# Audio-Beamformer_Supply_V1_0.net
KiCad netlist of a schematic drawn in Altium Designer
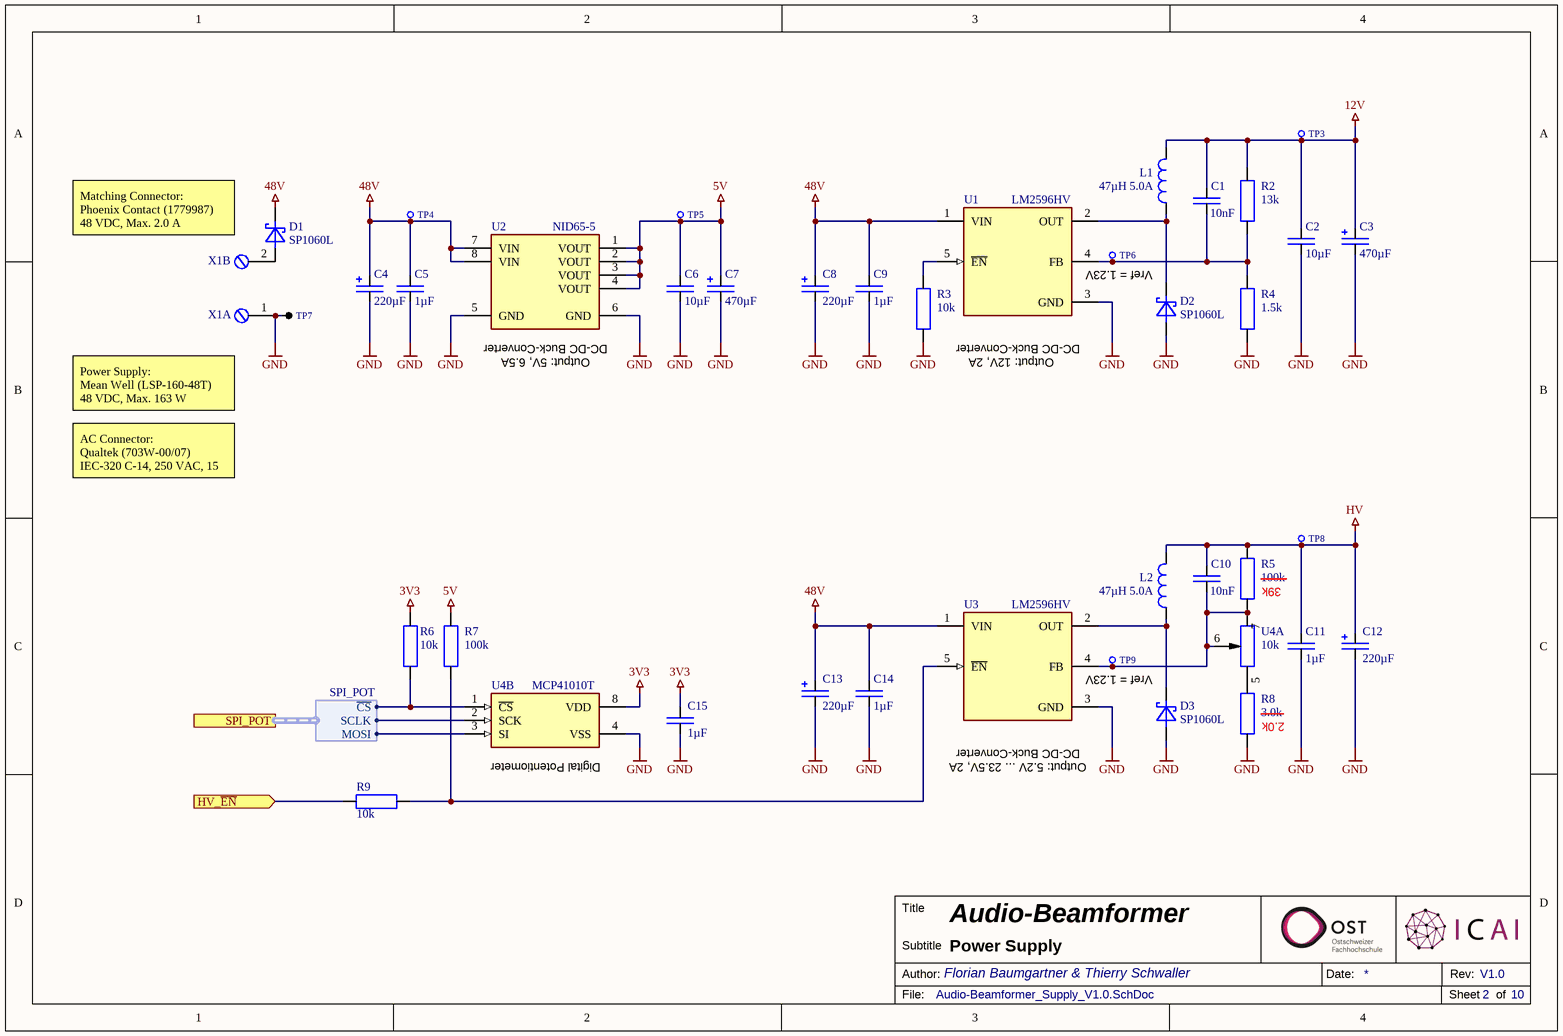
[diagram p0: Audio-Beamformer_Supply_V1.0.SchDoc]

(export (version "E")
  (design (tool "Eeschema 10.0.6"))
  (components
    (comp (ref "C1")
      (value "10nF")
      (footprint "SMD Keramikkondensator 0603")
      (description "SMD Ceramic Capacitor E6")
      (libsource (lib "Ceramic Capacitors-E6") (part "E6 - 10nF"))
    )
    (comp (ref "C2")
      (value "10µF")
      (footprint "SMD Keramikkondensator 1206")
      (description "CAP-MK")
      (libsource (lib "AudioAmp") (part "C-CAPACITOR"))
    )
    (comp (ref "C3")
      (value "470µF")
      (footprint "SMD Elko 10.0x10.0")
      (description "CAP-Elko")
      (libsource (lib "TFS Integrated Library") (part "C-ELCAP"))
    )
    (comp (ref "C4")
      (value "220µF")
      (footprint "SMD Elko 12.5x13.5")
      (description "CAP-Elko")
      (libsource (lib "TFS Integrated Library") (part "C-ELCAP"))
    )
    (comp (ref "C5")
      (value "1µF")
      (footprint "SMD Keramikkondensator 1206")
      (description "CAP-MK")
      (libsource (lib "AudioAmp") (part "C-CAPACITOR"))
    )
    (comp (ref "C6")
      (value "10µF")
      (footprint "SMD Keramikkondensator 1206")
      (description "CAP-MK")
      (libsource (lib "AudioAmp") (part "C-CAPACITOR"))
    )
    (comp (ref "C7")
      (value "470µF")
      (footprint "SMD Elko 10.0x10.0")
      (description "CAP-Elko")
      (libsource (lib "TFS Integrated Library") (part "C-ELCAP"))
    )
    (comp (ref "C8")
      (value "220µF")
      (footprint "SMD Elko 12.5x13.5")
      (description "CAP-Elko")
      (libsource (lib "TFS Integrated Library") (part "C-ELCAP"))
    )
    (comp (ref "C9")
      (value "1µF")
      (footprint "SMD Keramikkondensator 1206")
      (description "CAP-MK")
      (libsource (lib "AudioAmp") (part "C-CAPACITOR"))
    )
    (comp (ref "C10")
      (value "10nF")
      (footprint "SMD Keramikkondensator 0603")
      (description "SMD Ceramic Capacitor E6")
      (libsource (lib "Ceramic Capacitors-E6") (part "E6 - 10nF"))
    )
    (comp (ref "C11")
      (value "1µF")
      (footprint "SMD Keramikkondensator 1206")
      (description "CAP-MK")
      (libsource (lib "AudioAmp") (part "C-CAPACITOR"))
    )
    (comp (ref "C12")
      (value "220µF")
      (footprint "SMD Elko 12.5x13.5")
      (description "CAP-Elko")
      (libsource (lib "TFS Integrated Library") (part "C-ELCAP"))
    )
    (comp (ref "C13")
      (value "220µF")
      (footprint "SMD Elko 12.5x13.5")
      (description "CAP-Elko")
      (libsource (lib "TFS Integrated Library") (part "C-ELCAP"))
    )
    (comp (ref "C14")
      (value "1µF")
      (footprint "SMD Keramikkondensator 1206")
      (description "CAP-MK")
      (libsource (lib "AudioAmp") (part "C-CAPACITOR"))
    )
    (comp (ref "C15")
      (value "1µF")
      (footprint "SMD Keramikkondensator 0603")
      (description "SMD Ceramic Capacitor E6")
      (libsource (lib "Fleet-Monitor") (part "E6 - 1uF"))
    )
    (comp (ref "D1")
      (value "SP1060L")
      (footprint "SMD Diode TO-277")
      (description "S-DIODE")
      (libsource (lib "TFS Integrated Library") (part "R-DIODE{colon}SCHKY"))
    )
    (comp (ref "D2")
      (value "SP1060L")
      (footprint "SMD Diode TO-277")
      (description "S-DIODE")
      (libsource (lib "TFS Integrated Library") (part "R-DIODE{colon}SCHKY"))
    )
    (comp (ref "D3")
      (value "SP1060L")
      (footprint "SMD Diode TO-277")
      (description "S-DIODE")
      (libsource (lib "TFS Integrated Library") (part "R-DIODE{colon}SCHKY"))
    )
    (comp (ref "L1")
      (value "47µH 5.0A")
      (footprint "SMD Inductor 13.8x12.6x6.5")
      (description "Shielded Power Inductor")
      (libsource (lib "Nixie-Test") (part "L-COIL"))
    )
    (comp (ref "L2")
      (value "47µH 5.0A")
      (footprint "SMD Inductor 13.8x12.6x6.5")
      (description "Shielded Power Inductor")
      (libsource (lib "Nixie-Test") (part "L-COIL"))
    )
    (comp (ref "R2")
      (value "13k")
      (footprint "SMD Widerstand 0603")
      (description "RES (E=Heizwiderstand B=Messwandler)")
      (libsource (lib "") (part "R-RESISTOR_1"))
    )
    (comp (ref "R3")
      (value "10k")
      (footprint "SMD Widerstand 0603")
      (description "RES (E=Heizwiderstand B=Messwandler)")
      (libsource (lib "") (part "R-RESISTOR_1"))
    )
    (comp (ref "R4")
      (value "1.5k")
      (footprint "SMD Widerstand 0603")
      (description "RES (E=Heizwiderstand B=Messwandler)")
      (libsource (lib "TFS Integrated Library") (part "R-RESISTOR"))
    )
    (comp (ref "R5")
      (value "100k")
      (footprint "SMD Widerstand 0603")
      (description "RES (E=Heizwiderstand B=Messwandler)")
      (libsource (lib "") (part "R-RESISTOR_1"))
    )
    (comp (ref "R6")
      (value "10k")
      (footprint "SMD Widerstand 0603")
      (description "RES (E=Heizwiderstand B=Messwandler)")
      (libsource (lib "") (part "R-RESISTOR_1"))
    )
    (comp (ref "R7")
      (value "100k")
      (footprint "SMD Widerstand 0603")
      (description "RES (E=Heizwiderstand B=Messwandler)")
      (libsource (lib "") (part "R-RESISTOR_1"))
    )
    (comp (ref "R8")
      (value "3.0k")
      (footprint "SMD Widerstand 0603")
      (description "RES (E=Heizwiderstand B=Messwandler)")
      (libsource (lib "TFS Integrated Library") (part "R-RESISTOR"))
    )
    (comp (ref "R9")
      (value "10k")
      (footprint "SMD Widerstand 0603")
      (description "RES (E=Heizwiderstand B=Messwandler)")
      (libsource (lib "") (part "R-RESISTOR_2"))
    )
    (comp (ref "TP3")
      (value "X-TP")
      (footprint "THT Testpunkt Ø1mm")
      (description "Testpunkt")
      (libsource (lib "Teensy-DevBoard") (part "X-TP"))
    )
    (comp (ref "TP4")
      (value "X-TP")
      (footprint "THT Testpunkt Ø1mm")
      (description "Testpunkt")
      (libsource (lib "Teensy-DevBoard") (part "X-TP"))
    )
    (comp (ref "TP5")
      (value "X-TP")
      (footprint "THT Testpunkt Ø1mm")
      (description "Testpunkt")
      (libsource (lib "Teensy-DevBoard") (part "X-TP"))
    )
    (comp (ref "TP6")
      (value "X-TP")
      (footprint "THT Testpunkt Ø1mm")
      (description "Testpunkt")
      (libsource (lib "Teensy-DevBoard") (part "X-TP"))
    )
    (comp (ref "TP7")
      (value "Schwarz")
      (footprint "THT Messpunkt Ø2.54mm Schwarz")
      (description "Messpunkt")
      (libsource (lib "SwissSkills-MCU-Interface") (part "X-MP"))
    )
    (comp (ref "TP8")
      (value "X-TP")
      (footprint "THT Testpunkt Ø1mm")
      (description "Testpunkt")
      (libsource (lib "Teensy-DevBoard") (part "X-TP"))
    )
    (comp (ref "TP9")
      (value "X-TP")
      (footprint "THT Testpunkt Ø1mm")
      (description "Testpunkt")
      (libsource (lib "Teensy-DevBoard") (part "X-TP"))
    )
    (comp (ref "U1")
      (value "LM2596HV")
      (footprint "SMD IC TO-263-5")
      (description "High Power Switching Buck Converter")
      (libsource (lib "Audio-Beamformer") (part "U-LM2596HV"))
    )
    (comp (ref "U2")
      (value "NID65-5")
      (footprint "THT DC-DC-Converter (NID65-X)")
      (description "High Power Switching Buck Converter")
      (libsource (lib "Audio-Beamformer") (part "U-NID65-5"))
    )
    (comp (ref "U3")
      (value "LM2596HV")
      (footprint "SMD IC TO-263-5")
      (description "High Power Switching Buck Converter")
      (libsource (lib "Audio-Beamformer") (part "U-LM2596HV"))
    )
    (comp (ref "U4")
      (value "MCP41010T")
      (footprint "SMD IC SOIC-8")
      (libsource (lib "Audio-Beamformer") (part "U-MCP41010T"))
    )
    (comp (ref "X1")
      (value "X-Klemme (2-Pol)")
      (footprint "THT Schraubklemme Steckbar 2-Pol (1757242)")
      (libsource (lib "Quad-Current-Probe") (part "X-Klemme (2-Pol)"))
    )
  )
  (nets
    (net (code "2") (name "/HV_~{EN}") (class "Default")
      (node (ref "R9") (pin "2") (pinfunction "2_2") (pintype "passive"))
    )
    (net (code "3") (name "/MOSI") (class "Default")
      (node (ref "U4") (pin "3") (pinfunction "SI_3") (pintype "input"))
    )
    (net (code "4") (name "/SCLK") (class "Default")
      (node (ref "U4") (pin "2") (pinfunction "SCK_2") (pintype "input"))
    )
    (net (code "6") (name "/~{CS}") (class "Default")
      (node (ref "R6") (pin "1") (pinfunction "1_1") (pintype "passive"))
      (node (ref "U4") (pin "1") (pinfunction "~{CS}_1") (pintype "input"))
    )
    (net (code "7") (name "3V3") (class "Default")
      (node (ref "C15") (pin "2") (pinfunction "2_2") (pintype "passive"))
      (node (ref "R6") (pin "2") (pinfunction "2_2") (pintype "passive"))
      (node (ref "U4") (pin "8") (pinfunction "VDD_8") (pintype "power_in"))
    )
    (net (code "8") (name "5V") (class "Default")
      (node (ref "C6") (pin "2") (pinfunction "2_2") (pintype "passive"))
      (node (ref "C7") (pin "P") (pinfunction "+_P") (pintype "passive"))
      (node (ref "R7") (pin "2") (pinfunction "2_2") (pintype "passive"))
      (node (ref "TP5") (pin "1") (pinfunction "1_1") (pintype "passive"))
      (node (ref "U2") (pin "1") (pinfunction "VOUT_1") (pintype "power_in"))
      (node (ref "U2") (pin "2") (pinfunction "VOUT_2") (pintype "power_in"))
      (node (ref "U2") (pin "3") (pinfunction "VOUT_3") (pintype "power_in"))
      (node (ref "U2") (pin "4") (pinfunction "VOUT_4") (pintype "power_in"))
    )
    (net (code "9") (name "12V") (class "Default")
      (node (ref "C1") (pin "2") (pinfunction "2_2") (pintype "passive"))
      (node (ref "C2") (pin "2") (pinfunction "2_2") (pintype "passive"))
      (node (ref "C3") (pin "P") (pinfunction "+_P") (pintype "passive"))
      (node (ref "L1") (pin "1") (pinfunction "1_1") (pintype "passive"))
      (node (ref "R2") (pin "2") (pinfunction "2_2") (pintype "passive"))
      (node (ref "TP3") (pin "1") (pinfunction "1_1") (pintype "passive"))
    )
    (net (code "10") (name "48V") (class "Default")
      (node (ref "C13") (pin "P") (pinfunction "+_P") (pintype "passive"))
      (node (ref "C14") (pin "2") (pinfunction "2_2") (pintype "passive"))
      (node (ref "C4") (pin "P") (pinfunction "+_P") (pintype "passive"))
      (node (ref "C5") (pin "2") (pinfunction "2_2") (pintype "passive"))
      (node (ref "C8") (pin "P") (pinfunction "+_P") (pintype "passive"))
      (node (ref "C9") (pin "2") (pinfunction "2_2") (pintype "passive"))
      (node (ref "D1") (pin "K") (pinfunction "K_K") (pintype "passive"))
      (node (ref "TP4") (pin "1") (pinfunction "1_1") (pintype "passive"))
      (node (ref "U1") (pin "1") (pinfunction "VIN_1") (pintype "power_in"))
      (node (ref "U2") (pin "7") (pinfunction "VIN_7") (pintype "power_in"))
      (node (ref "U2") (pin "8") (pinfunction "VIN_8") (pintype "power_in"))
      (node (ref "U3") (pin "1") (pinfunction "VIN_1") (pintype "power_in"))
    )
    (net (code "11") (name "GND") (class "Default")
      (node (ref "C11") (pin "1") (pinfunction "1_1") (pintype "passive"))
      (node (ref "C12") (pin "M") (pinfunction "-_M") (pintype "passive"))
      (node (ref "C13") (pin "M") (pinfunction "-_M") (pintype "passive"))
      (node (ref "C14") (pin "1") (pinfunction "1_1") (pintype "passive"))
      (node (ref "C15") (pin "1") (pinfunction "1_1") (pintype "passive"))
      (node (ref "C2") (pin "1") (pinfunction "1_1") (pintype "passive"))
      (node (ref "C3") (pin "M") (pinfunction "-_M") (pintype "passive"))
      (node (ref "C4") (pin "M") (pinfunction "-_M") (pintype "passive"))
      (node (ref "C5") (pin "1") (pinfunction "1_1") (pintype "passive"))
      (node (ref "C6") (pin "1") (pinfunction "1_1") (pintype "passive"))
      (node (ref "C7") (pin "M") (pinfunction "-_M") (pintype "passive"))
      (node (ref "C8") (pin "M") (pinfunction "-_M") (pintype "passive"))
      (node (ref "C9") (pin "1") (pinfunction "1_1") (pintype "passive"))
      (node (ref "D2") (pin "A") (pinfunction "A_A") (pintype "passive"))
      (node (ref "D3") (pin "A") (pinfunction "A_A") (pintype "passive"))
      (node (ref "R3") (pin "1") (pinfunction "1_1") (pintype "passive"))
      (node (ref "R4") (pin "2") (pinfunction "2_2") (pintype "passive"))
      (node (ref "R8") (pin "2") (pinfunction "2_2") (pintype "passive"))
      (node (ref "TP7") (pin "1") (pinfunction "1_1") (pintype "passive"))
      (node (ref "U1") (pin "3") (pinfunction "GND_3") (pintype "power_in"))
      (node (ref "U2") (pin "5") (pinfunction "GND_5") (pintype "power_in"))
      (node (ref "U2") (pin "6") (pinfunction "GND_6") (pintype "power_in"))
      (node (ref "U3") (pin "3") (pinfunction "GND_3") (pintype "power_in"))
      (node (ref "U4") (pin "4") (pinfunction "VSS_4") (pintype "power_in"))
      (node (ref "X1") (pin "1") (pinfunction "1_1") (pintype "passive"))
    )
    (net (code "12") (name "HV") (class "Default")
      (node (ref "C10") (pin "2") (pinfunction "2_2") (pintype "passive"))
      (node (ref "C11") (pin "2") (pinfunction "2_2") (pintype "passive"))
      (node (ref "C12") (pin "P") (pinfunction "+_P") (pintype "passive"))
      (node (ref "L2") (pin "1") (pinfunction "1_1") (pintype "passive"))
      (node (ref "R5") (pin "2") (pinfunction "2_2") (pintype "passive"))
      (node (ref "TP8") (pin "1") (pinfunction "1_1") (pintype "passive"))
    )
    (net (code "13") (name "Net-(D1-PadA)") (class "Default")
      (node (ref "D1") (pin "A") (pinfunction "A_A") (pintype "passive"))
      (node (ref "X1") (pin "2") (pinfunction "2_2") (pintype "passive"))
    )
    (net (code "14") (name "Net-(U1-FB)") (class "Default")
      (node (ref "C1") (pin "1") (pinfunction "1_1") (pintype "passive"))
      (node (ref "R2") (pin "1") (pinfunction "1_1") (pintype "passive"))
      (node (ref "R4") (pin "1") (pinfunction "1_1") (pintype "passive"))
      (node (ref "TP6") (pin "1") (pinfunction "1_1") (pintype "passive"))
      (node (ref "U1") (pin "4") (pinfunction "FB_4") (pintype "passive"))
    )
    (net (code "15") (name "Net-(U1-OUT)") (class "Default")
      (node (ref "D2") (pin "K") (pinfunction "K_K") (pintype "passive"))
      (node (ref "L1") (pin "2") (pinfunction "2_2") (pintype "passive"))
      (node (ref "U1") (pin "2") (pinfunction "OUT_2") (pintype "passive"))
    )
    (net (code "16") (name "Net-(U1-~{EN})") (class "Default")
      (node (ref "R3") (pin "2") (pinfunction "2_2") (pintype "passive"))
      (node (ref "U1") (pin "5") (pinfunction "~{EN}_5") (pintype "input"))
    )
    (net (code "17") (name "Net-(U3-FB)") (class "Default")
      (node (ref "C10") (pin "1") (pinfunction "1_1") (pintype "passive"))
      (node (ref "R5") (pin "1") (pinfunction "1_1") (pintype "passive"))
      (node (ref "TP9") (pin "1") (pinfunction "1_1") (pintype "passive"))
      (node (ref "U3") (pin "4") (pinfunction "FB_4") (pintype "passive"))
      (node (ref "U4") (pin "6") (pinfunction "M_6") (pintype "passive"))
      (node (ref "U4") (pin "7") (pinfunction "L_7") (pintype "passive"))
    )
    (net (code "18") (name "Net-(U3-OUT)") (class "Default")
      (node (ref "D3") (pin "K") (pinfunction "K_K") (pintype "passive"))
      (node (ref "L2") (pin "2") (pinfunction "2_2") (pintype "passive"))
      (node (ref "U3") (pin "2") (pinfunction "OUT_2") (pintype "passive"))
    )
    (net (code "19") (name "Net-(U3-~{EN})") (class "Default")
      (node (ref "R7") (pin "1") (pinfunction "1_1") (pintype "passive"))
      (node (ref "R9") (pin "1") (pinfunction "1_1") (pintype "passive"))
      (node (ref "U3") (pin "5") (pinfunction "~{EN}_5") (pintype "input"))
    )
    (net (code "20") (name "Net-(U4A-H)") (class "Default")
      (node (ref "R8") (pin "1") (pinfunction "1_1") (pintype "passive"))
      (node (ref "U4") (pin "5") (pinfunction "H_5") (pintype "passive"))
    )
    (net (code "21") (name "unconnected-(U2-NC-Pad9)") (class "Default")
      (node (ref "U2") (pin "9") (pinfunction "NC_9") (pintype "passive"))
    )
    (net (code "22") (name "unconnected-(U2-NC-Pad10)") (class "Default")
      (node (ref "U2") (pin "10") (pinfunction "NC_10") (pintype "passive"))
    )
    (net (code "23") (name "unconnected-(U2-NC-Pad11)") (class "Default")
      (node (ref "U2") (pin "11") (pinfunction "NC_11") (pintype "passive"))
    )
    (net (code "24") (name "unconnected-(U4B-NC-Pad7)") (class "Default")
      (node (ref "U4") (pin "7") (pinfunction "NC_7") (pintype "passive"))
    )
    (net (code "25") (name "unconnected-(U4B-NC-Pad8)") (class "Default")
      (node (ref "U4") (pin "8") (pinfunction "NC_8") (pintype "passive"))
    )
    (net (code "26") (name "unconnected-(U4B-NC-Pad9)") (class "Default")
      (node (ref "U4") (pin "9") (pinfunction "NC_9") (pintype "passive"))
    )
    (net (code "27") (name "unconnected-(U4B-NC-Pad12)") (class "Default")
      (node (ref "U4") (pin "12") (pinfunction "NC_12") (pintype "passive"))
    )
    (net (code "28") (name "unconnected-(U4B-NC-Pad13)") (class "Default")
      (node (ref "U4") (pin "13") (pinfunction "NC_13") (pintype "passive"))
    )
  )
)
